# Main.net
KiCad netlist of a schematic drawn in Altium Designer
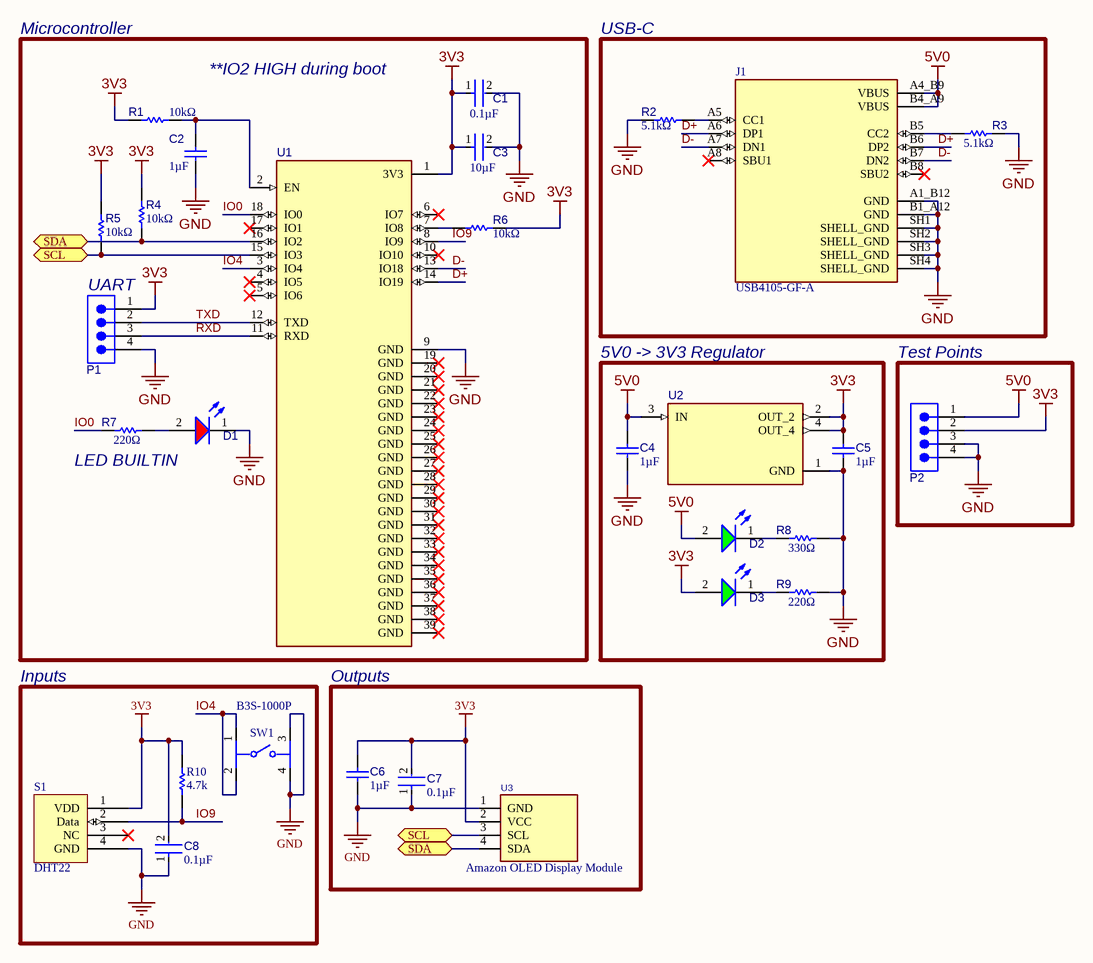
[diagram p0: Main.SchDoc]

(export (version "E")
  (design (tool "Eeschema 10.0.6"))
  (components
    (comp (ref "C1")
      (value "0.1µF")
      (footprint "FP-C1206C-EB-MFG")
      (description "CAP CER 0.1UF 100V X7R 1206")
      (fields
        (field (name "TOLERANCE") "0.1")
        (field (name "OCTOPART") "https://octopart.com/c1206c104k1ractu-kemet-89521")
      )
      (libsource (lib "Altium Content Vault") (part "b4654b650e69147ec39a6b967a45e02"))
    )
    (comp (ref "C2")
      (value "1µF")
      (footprint "CAPC3216X110X50LL20T25")
      (description "Chip Capacitor, 1 uF, +/- 10%, 50 V, -55 to 125 degC, 1206 (3216 Metric), RoHS, Tape and Reel")
      (fields (field (name "MANUFACTURER") "Kemet") (field (name "TOLERANCE") "10%"))
      (libsource (lib "Altium Content Vault") (part "CAP-NP-2"))
    )
    (comp (ref "C3")
      (value "10µF")
      (footprint "FP-GRM31C-0_2-e0_3_0_8-MFG")
      (description "Chip Multilayer Ceramic Capacitors for General Purpose, 1206, 10uF, X7R, 15%, 10%, 25V")
      (fields (field (name "TOLERANCE") "10%") (field (name "VOLTAGE") "25V"))
      (libsource (lib "Altium Content Vault") (part "02cd4be3c70576c341d710602a673aa"))
    )
    (comp (ref "C4")
      (value "1µF")
      (footprint "CAPC3216X110X50LL20T25")
      (description "Chip Capacitor, 1 uF, +/- 10%, 50 V, -55 to 125 degC, 1206 (3216 Metric), RoHS, Tape and Reel")
      (fields (field (name "MANUFACTURER") "Kemet") (field (name "TOLERANCE") "10%"))
      (libsource (lib "Altium Content Vault") (part "CAP-NP-2"))
    )
    (comp (ref "C5")
      (value "1µF")
      (footprint "CAPC3216X110X50LL20T25")
      (description "Chip Capacitor, 1 uF, +/- 10%, 50 V, -55 to 125 degC, 1206 (3216 Metric), RoHS, Tape and Reel")
      (fields (field (name "MANUFACTURER") "Kemet") (field (name "TOLERANCE") "10%"))
      (libsource (lib "Altium Content Vault") (part "CAP-NP-2"))
    )
    (comp (ref "C6")
      (value "1µF")
      (footprint "CAPC3216X110X50LL20T25")
      (description "Chip Capacitor, 1 uF, +/- 10%, 50 V, -55 to 125 degC, 1206 (3216 Metric), RoHS, Tape and Reel")
      (fields (field (name "MANUFACTURER") "Kemet") (field (name "TOLERANCE") "10%"))
      (libsource (lib "Altium Content Vault") (part "CAP-NP-2"))
    )
    (comp (ref "C7")
      (value "0.1µF")
      (footprint "FP-C1206C-EB-MFG")
      (description "CAP CER 0.1UF 100V X7R 1206")
      (fields
        (field (name "TOLERANCE") "0.1")
        (field (name "OCTOPART") "https://octopart.com/c1206c104k1ractu-kemet-89521")
      )
      (libsource (lib "Altium Content Vault") (part "b4654b650e69147ec39a6b967a45e02"))
    )
    (comp (ref "C8")
      (value "0.1µF")
      (footprint "FP-C1206C-EB-MFG")
      (description "CAP CER 0.1UF 100V X7R 1206")
      (fields
        (field (name "TOLERANCE") "0.1")
        (field (name "OCTOPART") "https://octopart.com/c1206c104k1ractu-kemet-89521")
      )
      (libsource (lib "Altium Content Vault") (part "b4654b650e69147ec39a6b967a45e02"))
    )
    (comp (ref "D1")
      (value "150120SS75000")
      (footprint "WL-SMCW_1206_150120xx75000")
      (description "Led, Red, 630 Nm, 1.9 V, 30 Ma, 60 Mcd Rohs Compliant: Yes")
      (libsource (lib "Altium Content Vault") (part "LED_Red_2A-1K"))
    )
    (comp (ref "D2")
      (value "150120GS75000")
      (footprint "WL-SMCW_1206_150120xx75000")
      (description "WL-SMCW SMT Mono-Color Chip LED Waterclear")
      (libsource (lib "Altium Content Vault") (part "LED_Green_2A-1K"))
    )
    (comp (ref "D3")
      (value "150120GS75000")
      (footprint "WL-SMCW_1206_150120xx75000")
      (description "WL-SMCW SMT Mono-Color Chip LED Waterclear")
      (libsource (lib "Altium Content Vault") (part "LED_Green_2A-1K"))
    )
    (comp (ref "J1")
      (value "USB4105-GF-A")
      (footprint "GCT_USB4105-GF-A")
      (fields (field (name "MF") "{'manufacturer': u'GCT'}"))
      (libsource (lib "USB4105-GF-A") (part "USB4105-GF-A"))
    )
    (comp (ref "P1")
      (value "61300411121")
      (footprint "61300411121")
      (description "WR-PHD Pin Header, THT, Vertical, pitch 2.54mm, 1 Row, 4P")
      (fields (field (name "MANUFACTURER") "Wurth Elektronik"))
      (libsource (lib "Altium_WR-PHD_rev24a") (part "61300411121"))
    )
    (comp (ref "P2")
      (value "61300411121")
      (footprint "61300411121")
      (description "WR-PHD Pin Header, THT, Vertical, pitch 2.54mm, 1 Row, 4P")
      (fields (field (name "MANUFACTURER") "Wurth Elektronik"))
      (libsource (lib "Altium_WR-PHD_rev24a") (part "61300411121"))
    )
    (comp (ref "R1")
      (value "10kΩ")
      (footprint "RESC3216X70X50LL20T25")
      (fields (field (name "MANUFACTURER") "Panasonic") (field (name "PART NUMBER") "ERA8AEB103V"))
      (libsource (lib "Altium Content Vault") (part "RES"))
    )
    (comp (ref "R2")
      (value "5.1kΩ")
      (footprint "RESC3216X70X50NL05T20")
      (fields (field (name "PART NUMBER") "ERJ-8ENF5101V") (field (name "MANUFACTURER") "Panasonic"))
      (libsource (lib "Altium Content Vault") (part "RES"))
    )
    (comp (ref "R3")
      (value "5.1kΩ")
      (footprint "RESC3216X70X50NL05T20")
      (fields (field (name "PART NUMBER") "ERJ-8ENF5101V") (field (name "MANUFACTURER") "Panasonic"))
      (libsource (lib "Altium Content Vault") (part "RES"))
    )
    (comp (ref "R4")
      (value "10kΩ")
      (footprint "RESC3216X70X50LL20T25")
      (fields (field (name "MANUFACTURER") "Panasonic") (field (name "PART NUMBER") "ERA8AEB103V"))
      (libsource (lib "Altium Content Vault") (part "RES"))
    )
    (comp (ref "R5")
      (value "10kΩ")
      (footprint "RESC3216X70X50LL20T25")
      (fields (field (name "MANUFACTURER") "Panasonic") (field (name "PART NUMBER") "ERA8AEB103V"))
      (libsource (lib "Altium Content Vault") (part "RES"))
    )
    (comp (ref "R6")
      (value "10kΩ")
      (footprint "RESC3216X70X50LL20T25")
      (fields (field (name "MANUFACTURER") "Panasonic") (field (name "PART NUMBER") "ERA8AEB103V"))
      (libsource (lib "Altium Content Vault") (part "RES"))
    )
    (comp (ref "R7")
      (value "220Ω")
      (footprint "RESC3216X70X50ML20T25")
      (fields (field (name "PART NUMBER") "ERA8AEB221V") (field (name "MANUFACTURER") "Panasonic"))
      (libsource (lib "Altium Content Vault") (part "RES"))
    )
    (comp (ref "R8")
      (value "330Ω")
      (footprint "RESC3216X70X50NL05T20")
      (fields (field (name "MANUFACTURER") "Panasonic") (field (name "PART NUMBER") "ERJ-8GEYJ331V"))
      (libsource (lib "Altium Content Vault") (part "RES"))
    )
    (comp (ref "R9")
      (value "220Ω")
      (footprint "RESC3216X70X50ML20T25")
      (fields (field (name "PART NUMBER") "ERA8AEB221V") (field (name "MANUFACTURER") "Panasonic"))
      (libsource (lib "Altium Content Vault") (part "RES"))
    )
    (comp (ref "R10")
      (value "4.7k")
      (footprint "RESC3216X70X50LL05T20")
      (fields (field (name "PART NUMBER") "ERJ8ENF4701V") (field (name "MANUFACTURER") "Panasonic"))
      (libsource (lib "Altium Content Vault") (part "RES"))
    )
    (comp (ref "S1")
      (value "DHT22")
      (footprint "DHT22_Footprint")
      (description "DHT22 Sensor")
      (libsource (lib "DHT22-Library") (part "DHT22"))
    )
    (comp (ref "SW1")
      (value "B3S-1000P")
      (footprint "FP-B3S-1000P-MFG")
      (description "SWITCH TACTILE SPST-NO 0.05A 24V")
      (libsource (lib "Altium Content Vault") (part "b8895f3f4cefb76e1819d2863dba89b"))
    )
    (comp (ref "U1")
      (value "ESP32-C3-WROOM-02-N4")
      (footprint "MODULE_ESP32-C3-WROOM-02-H4")
      (fields (field (name "MF") "Espressif Systems"))
      (libsource (lib "ESP32-C3-WROOM-02-N4") (part "ESP32-C3-WROOM-02-N4"))
    )
    (comp (ref "U2")
      (value "TLV1117LV33DCYR")
      (footprint "VREG_TLV1117LV33DCYR")
      (description "1-A, low-dropout voltage regulator")
      (fields (field (name "DIGI-KEY_PART_NUMBER") "296-28778-2-ND") (field (name "MF") "Texas Instruments"))
      (libsource (lib "TLV1117LV33DCYR") (part "TLV1117LV33DCYR"))
    )
    (comp (ref "U3")
      (value "Amazon OLED Display Module")
      (footprint "Amazon OLED Display Module")
      (description "Hosyond 5 Pcs 0.96 Inch OLED I2C Display Module 128x64 Pixel OLED Display")
      (libsource (lib "RIT-EVT-Vault") (part "Amazon OLED Display Module"))
    )
  )
  (nets
    (net (code "1") (name "/D+") (class "Default")
      (node (ref "J1") (pin "A6") (pinfunction "DP1_A6") (pintype "bidirectional"))
      (node (ref "J1") (pin "B6") (pinfunction "DP2_B6") (pintype "bidirectional"))
      (node (ref "U1") (pin "14") (pinfunction "IO19_14") (pintype "bidirectional"))
    )
    (net (code "2") (name "/D-") (class "Default")
      (node (ref "J1") (pin "A7") (pinfunction "DN1_A7") (pintype "bidirectional"))
      (node (ref "J1") (pin "B7") (pinfunction "DN2_B7") (pintype "bidirectional"))
      (node (ref "U1") (pin "13") (pinfunction "IO18_13") (pintype "bidirectional"))
    )
    (net (code "3") (name "/IO0") (class "Default")
      (node (ref "R7") (pin "1") (pinfunction "1_1") (pintype "passive"))
      (node (ref "U1") (pin "18") (pinfunction "IO0_18") (pintype "bidirectional"))
    )
    (net (code "4") (name "/IO4") (class "Default")
      (node (ref "SW1") (pin "1") (pinfunction "1_1") (pintype "passive"))
      (node (ref "SW1") (pin "2") (pinfunction "2_2") (pintype "passive"))
      (node (ref "U1") (pin "3") (pinfunction "IO4_3") (pintype "bidirectional"))
    )
    (net (code "5") (name "/IO9") (class "Default")
      (node (ref "R10") (pin "1") (pinfunction "1_1") (pintype "passive"))
      (node (ref "S1") (pin "2") (pinfunction "Data_2") (pintype "bidirectional"))
      (node (ref "U1") (pin "8") (pinfunction "IO9_8") (pintype "bidirectional"))
    )
    (net (code "6") (name "/RXD") (class "Default")
      (node (ref "P1") (pin "3") (pinfunction "3_3") (pintype "passive"))
      (node (ref "U1") (pin "11") (pinfunction "RXD_11") (pintype "bidirectional"))
    )
    (net (code "7") (name "/SCL") (class "Default")
      (node (ref "R5") (pin "1") (pinfunction "1_1") (pintype "passive"))
      (node (ref "U1") (pin "15") (pinfunction "IO3_15") (pintype "bidirectional"))
      (node (ref "U3") (pin "3") (pinfunction "SCL_3") (pintype "passive"))
    )
    (net (code "8") (name "/SDA") (class "Default")
      (node (ref "R4") (pin "1") (pinfunction "1_1") (pintype "passive"))
      (node (ref "U1") (pin "16") (pinfunction "IO2_16") (pintype "bidirectional"))
      (node (ref "U3") (pin "4") (pinfunction "SDA_4") (pintype "passive"))
    )
    (net (code "9") (name "/TXD") (class "Default")
      (node (ref "P1") (pin "2") (pinfunction "2_2") (pintype "passive"))
      (node (ref "U1") (pin "12") (pinfunction "TXD_12") (pintype "bidirectional"))
    )
    (net (code "10") (name "3V3") (class "Default")
      (node (ref "C1") (pin "1") (pinfunction "1_1") (pintype "passive"))
      (node (ref "C3") (pin "1") (pinfunction "1_1") (pintype "passive"))
      (node (ref "C5") (pin "2") (pinfunction "2_2") (pintype "passive"))
      (node (ref "C6") (pin "2") (pinfunction "2_2") (pintype "passive"))
      (node (ref "C7") (pin "2") (pinfunction "2_2") (pintype "passive"))
      (node (ref "C8") (pin "2") (pinfunction "2_2") (pintype "passive"))
      (node (ref "D3") (pin "2") (pinfunction "A_2") (pintype "passive"))
      (node (ref "P1") (pin "1") (pinfunction "1_1") (pintype "passive"))
      (node (ref "P2") (pin "2") (pinfunction "2_2") (pintype "passive"))
      (node (ref "R1") (pin "1") (pinfunction "1_1") (pintype "passive"))
      (node (ref "R10") (pin "2") (pinfunction "2_2") (pintype "passive"))
      (node (ref "R4") (pin "2") (pinfunction "2_2") (pintype "passive"))
      (node (ref "R5") (pin "2") (pinfunction "2_2") (pintype "passive"))
      (node (ref "R6") (pin "2") (pinfunction "2_2") (pintype "passive"))
      (node (ref "S1") (pin "1") (pinfunction "VDD_1") (pintype "power_in"))
      (node (ref "U1") (pin "1") (pinfunction "3V3_1") (pintype "power_in"))
      (node (ref "U2") (pin "2") (pinfunction "OUT_2_2") (pintype "output"))
      (node (ref "U2") (pin "4") (pinfunction "OUT_4_4") (pintype "output"))
      (node (ref "U3") (pin "2") (pinfunction "VCC_2") (pintype "passive"))
    )
    (net (code "11") (name "5V0") (class "Default")
      (node (ref "C4") (pin "2") (pinfunction "2_2") (pintype "passive"))
      (node (ref "D2") (pin "2") (pinfunction "A_2") (pintype "passive"))
      (node (ref "J1") (pin "A4_B9") (pinfunction "VBUS_A4_B9") (pintype "power_in"))
      (node (ref "J1") (pin "B4_A9") (pinfunction "VBUS_B4_A9") (pintype "power_in"))
      (node (ref "P2") (pin "1") (pinfunction "1_1") (pintype "passive"))
      (node (ref "U2") (pin "3") (pinfunction "IN_3") (pintype "input"))
    )
    (net (code "12") (name "GND") (class "Default")
      (node (ref "C1") (pin "2") (pinfunction "2_2") (pintype "passive"))
      (node (ref "C2") (pin "1") (pinfunction "1_1") (pintype "passive"))
      (node (ref "C3") (pin "2") (pinfunction "2_2") (pintype "passive"))
      (node (ref "C4") (pin "1") (pinfunction "1_1") (pintype "passive"))
      (node (ref "C5") (pin "1") (pinfunction "1_1") (pintype "passive"))
      (node (ref "C6") (pin "1") (pinfunction "1_1") (pintype "passive"))
      (node (ref "C7") (pin "1") (pinfunction "1_1") (pintype "passive"))
      (node (ref "C8") (pin "1") (pinfunction "1_1") (pintype "passive"))
      (node (ref "D1") (pin "1") (pinfunction "K_1") (pintype "passive"))
      (node (ref "J1") (pin "A1_B12") (pinfunction "GND_A1_B12") (pintype "power_in"))
      (node (ref "J1") (pin "B1_A12") (pinfunction "GND_B1_A12") (pintype "power_in"))
      (node (ref "J1") (pin "SH1") (pinfunction "SHELL_GND_SH1") (pintype "power_in"))
      (node (ref "J1") (pin "SH2") (pinfunction "SHELL_GND_SH2") (pintype "power_in"))
      (node (ref "J1") (pin "SH3") (pinfunction "SHELL_GND_SH3") (pintype "power_in"))
      (node (ref "J1") (pin "SH4") (pinfunction "SHELL_GND_SH4") (pintype "power_in"))
      (node (ref "P1") (pin "4") (pinfunction "4_4") (pintype "passive"))
      (node (ref "P2") (pin "3") (pinfunction "3_3") (pintype "passive"))
      (node (ref "P2") (pin "4") (pinfunction "4_4") (pintype "passive"))
      (node (ref "R2") (pin "1") (pinfunction "1_1") (pintype "passive"))
      (node (ref "R3") (pin "2") (pinfunction "2_2") (pintype "passive"))
      (node (ref "R8") (pin "2") (pinfunction "2_2") (pintype "passive"))
      (node (ref "R9") (pin "2") (pinfunction "2_2") (pintype "passive"))
      (node (ref "S1") (pin "4") (pinfunction "GND_4") (pintype "passive"))
      (node (ref "SW1") (pin "3") (pinfunction "3_3") (pintype "passive"))
      (node (ref "SW1") (pin "4") (pinfunction "4_4") (pintype "passive"))
      (node (ref "U1") (pin "9") (pinfunction "GND_9") (pintype "power_in"))
      (node (ref "U2") (pin "1") (pinfunction "GND_1") (pintype "power_in"))
      (node (ref "U3") (pin "1") (pinfunction "GND_1") (pintype "passive"))
    )
    (net (code "13") (name "Net-(D1-A)") (class "Default")
      (node (ref "D1") (pin "2") (pinfunction "A_2") (pintype "passive"))
      (node (ref "R7") (pin "2") (pinfunction "2_2") (pintype "passive"))
    )
    (net (code "14") (name "Net-(D2-K)") (class "Default")
      (node (ref "D2") (pin "1") (pinfunction "K_1") (pintype "passive"))
      (node (ref "R8") (pin "1") (pinfunction "1_1") (pintype "passive"))
    )
    (net (code "15") (name "Net-(D3-K)") (class "Default")
      (node (ref "D3") (pin "1") (pinfunction "K_1") (pintype "passive"))
      (node (ref "R9") (pin "1") (pinfunction "1_1") (pintype "passive"))
    )
    (net (code "16") (name "Net-(J1-CC1)") (class "Default")
      (node (ref "J1") (pin "A5") (pinfunction "CC1_A5") (pintype "bidirectional"))
      (node (ref "R2") (pin "2") (pinfunction "2_2") (pintype "passive"))
    )
    (net (code "17") (name "Net-(J1-CC2)") (class "Default")
      (node (ref "J1") (pin "B5") (pinfunction "CC2_B5") (pintype "bidirectional"))
      (node (ref "R3") (pin "1") (pinfunction "1_1") (pintype "passive"))
    )
    (net (code "18") (name "Net-(U1-EN)") (class "Default")
      (node (ref "C2") (pin "2") (pinfunction "2_2") (pintype "passive"))
      (node (ref "R1") (pin "2") (pinfunction "2_2") (pintype "passive"))
      (node (ref "U1") (pin "2") (pinfunction "EN_2") (pintype "input"))
    )
    (net (code "19") (name "Net-(U1-IO8)") (class "Default")
      (node (ref "R6") (pin "1") (pinfunction "1_1") (pintype "passive"))
      (node (ref "U1") (pin "7") (pinfunction "IO8_7") (pintype "bidirectional"))
    )
    (net (code "20") (name "unconnected-(J1-SBU1-PadA8)") (class "Default")
      (node (ref "J1") (pin "A8") (pinfunction "SBU1_A8") (pintype "bidirectional+no_connect"))
    )
    (net (code "21") (name "unconnected-(J1-SBU2-PadB8)") (class "Default")
      (node (ref "J1") (pin "B8") (pinfunction "SBU2_B8") (pintype "bidirectional+no_connect"))
    )
    (net (code "22") (name "unconnected-(S1-NC-Pad3)") (class "Default")
      (node (ref "S1") (pin "3") (pinfunction "NC_3") (pintype "passive+no_connect"))
    )
    (net (code "23") (name "unconnected-(U1-GND-Pad19)") (class "Default")
      (node (ref "U1") (pin "19") (pinfunction "GND_19") (pintype "power_in+no_connect"))
    )
    (net (code "24") (name "unconnected-(U1-GND-Pad20)") (class "Default")
      (node (ref "U1") (pin "20") (pinfunction "GND_20") (pintype "power_in+no_connect"))
    )
    (net (code "25") (name "unconnected-(U1-GND-Pad21)") (class "Default")
      (node (ref "U1") (pin "21") (pinfunction "GND_21") (pintype "power_in+no_connect"))
    )
    (net (code "26") (name "unconnected-(U1-GND-Pad22)") (class "Default")
      (node (ref "U1") (pin "22") (pinfunction "GND_22") (pintype "power_in+no_connect"))
    )
    (net (code "27") (name "unconnected-(U1-GND-Pad23)") (class "Default")
      (node (ref "U1") (pin "23") (pinfunction "GND_23") (pintype "power_in+no_connect"))
    )
    (net (code "28") (name "unconnected-(U1-GND-Pad24)") (class "Default")
      (node (ref "U1") (pin "24") (pinfunction "GND_24") (pintype "power_in+no_connect"))
    )
    (net (code "29") (name "unconnected-(U1-GND-Pad25)") (class "Default")
      (node (ref "U1") (pin "25") (pinfunction "GND_25") (pintype "power_in+no_connect"))
    )
    (net (code "30") (name "unconnected-(U1-GND-Pad26)") (class "Default")
      (node (ref "U1") (pin "26") (pinfunction "GND_26") (pintype "power_in+no_connect"))
    )
    (net (code "31") (name "unconnected-(U1-GND-Pad27)") (class "Default")
      (node (ref "U1") (pin "27") (pinfunction "GND_27") (pintype "power_in+no_connect"))
    )
    (net (code "32") (name "unconnected-(U1-GND-Pad28)") (class "Default")
      (node (ref "U1") (pin "28") (pinfunction "GND_28") (pintype "power_in+no_connect"))
    )
    (net (code "33") (name "unconnected-(U1-GND-Pad29)") (class "Default")
      (node (ref "U1") (pin "29") (pinfunction "GND_29") (pintype "power_in+no_connect"))
    )
    (net (code "34") (name "unconnected-(U1-GND-Pad30)") (class "Default")
      (node (ref "U1") (pin "30") (pinfunction "GND_30") (pintype "power_in+no_connect"))
    )
    (net (code "35") (name "unconnected-(U1-GND-Pad31)") (class "Default")
      (node (ref "U1") (pin "31") (pinfunction "GND_31") (pintype "power_in+no_connect"))
    )
    (net (code "36") (name "unconnected-(U1-GND-Pad32)") (class "Default")
      (node (ref "U1") (pin "32") (pinfunction "GND_32") (pintype "power_in+no_connect"))
    )
    (net (code "37") (name "unconnected-(U1-GND-Pad33)") (class "Default")
      (node (ref "U1") (pin "33") (pinfunction "GND_33") (pintype "power_in+no_connect"))
    )
    (net (code "38") (name "unconnected-(U1-GND-Pad34)") (class "Default")
      (node (ref "U1") (pin "34") (pinfunction "GND_34") (pintype "power_in+no_connect"))
    )
    (net (code "39") (name "unconnected-(U1-GND-Pad35)") (class "Default")
      (node (ref "U1") (pin "35") (pinfunction "GND_35") (pintype "power_in+no_connect"))
    )
    (net (code "40") (name "unconnected-(U1-GND-Pad36)") (class "Default")
      (node (ref "U1") (pin "36") (pinfunction "GND_36") (pintype "power_in+no_connect"))
    )
    (net (code "41") (name "unconnected-(U1-GND-Pad37)") (class "Default")
      (node (ref "U1") (pin "37") (pinfunction "GND_37") (pintype "power_in+no_connect"))
    )
    (net (code "42") (name "unconnected-(U1-GND-Pad38)") (class "Default")
      (node (ref "U1") (pin "38") (pinfunction "GND_38") (pintype "power_in+no_connect"))
    )
    (net (code "43") (name "unconnected-(U1-GND-Pad39)") (class "Default")
      (node (ref "U1") (pin "39") (pinfunction "GND_39") (pintype "power_in+no_connect"))
    )
    (net (code "44") (name "unconnected-(U1-IO1-Pad17)") (class "Default")
      (node (ref "U1") (pin "17") (pinfunction "IO1_17") (pintype "bidirectional+no_connect"))
    )
    (net (code "45") (name "unconnected-(U1-IO5-Pad4)") (class "Default")
      (node (ref "U1") (pin "4") (pinfunction "IO5_4") (pintype "bidirectional+no_connect"))
    )
    (net (code "46") (name "unconnected-(U1-IO6-Pad5)") (class "Default")
      (node (ref "U1") (pin "5") (pinfunction "IO6_5") (pintype "bidirectional+no_connect"))
    )
    (net (code "47") (name "unconnected-(U1-IO7-Pad6)") (class "Default")
      (node (ref "U1") (pin "6") (pinfunction "IO7_6") (pintype "bidirectional+no_connect"))
    )
    (net (code "48") (name "unconnected-(U1-IO10-Pad10)") (class "Default")
      (node (ref "U1") (pin "10") (pinfunction "IO10_10") (pintype "bidirectional+no_connect"))
    )
  )
)
